# Temp_Probe_Section.net
KiCad netlist of a schematic drawn in Altium Designer
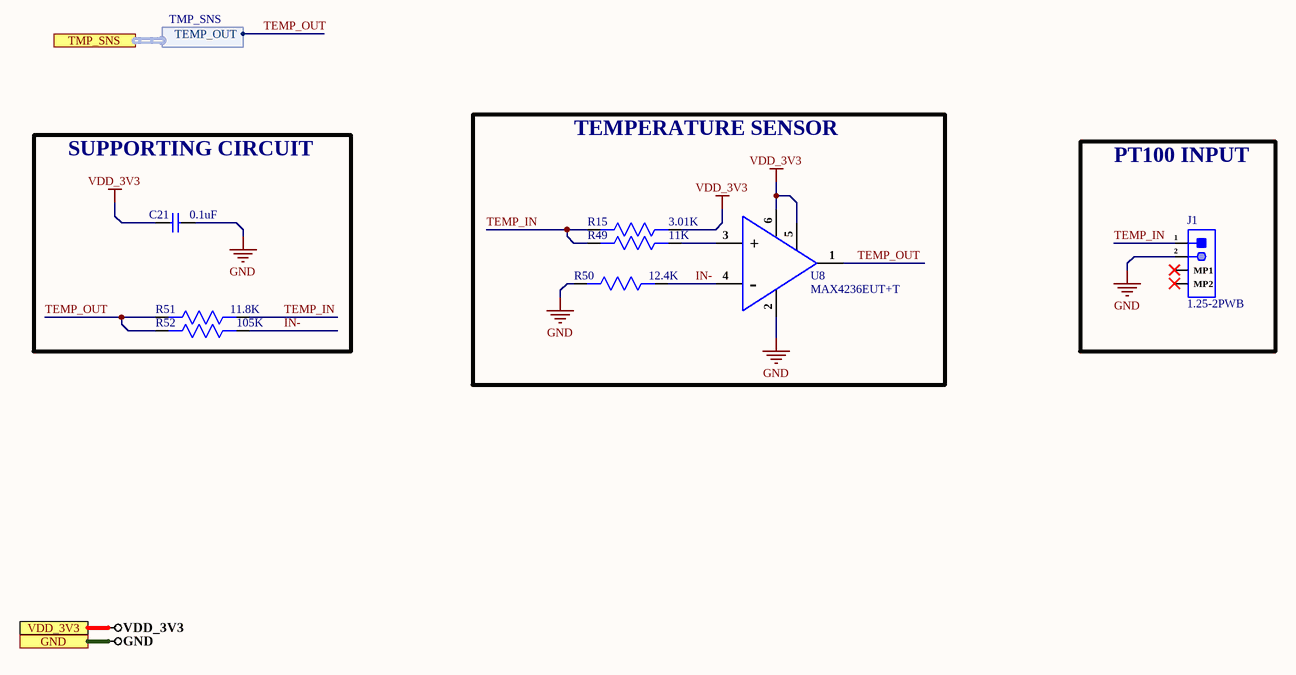
[diagram p0: Temp_Probe_Section.SchDoc]

(export (version "E")
  (design (tool "Eeschema 10.0.6"))
  (components
    (comp (ref "C21")
      (value "0.1uF")
      (footprint "Cap 0603")
      (description "Cap Ceramic 0.1uF 50VDC X7R 10% SMD 0603 Paper T/R")
      (fields
        (field (name "MANUFACTURER") "Samsung")
        (field (name "MANUFACTURER PART NUMBER") "CL10B104KB8NNNC")
      )
      (libsource (lib "Cole_Benson") (part "CL10B104KB8NNNC"))
    )
    (comp (ref "J1")
      (value "1.25-2PWB")
      (footprint "1.25-2PWB")
      (fields (field (name "MANUFACTURER") "DEALON") (field (name "LCSC PART NUMBER") "C2905009"))
      (libsource (lib "Cole_Benson") (part "1.25-2PWB"))
    )
    (comp (ref "R15")
      (value "3.01K")
      (footprint "Res0603")
      (description "RES SMD 3.01K OHM 1% 1/10W 0603")
      (fields
        (field (name "MANUFACTURER") "Panasonic")
        (field (name "MANUFACTURER PART NUMBER") "ERJ-3EKF3011V")
      )
      (libsource (lib "Cole_Benson") (part "ERJ3EKF3011V"))
    )
    (comp (ref "R49")
      (value "11K")
      (footprint "Res0603")
      (description "RES SMD 11K, 1%, 0.1W, 0603")
      (fields
        (field (name "MANUFACTURER") "Yageo")
        (field (name "MANUFACTURER PART NUMBER") "RC0603FR-0711KL")
      )
      (libsource (lib "Cole_Benson") (part "RC0603FR-0711KL"))
    )
    (comp (ref "R50")
      (value "12.4K")
      (footprint "Res0603")
      (description "RES SMD 12.4K OHM 1% 1/10W 0603")
      (fields
        (field (name "MANUFACTURER") "Yageo")
        (field (name "MANUFACTURER PART NUMBER") "RC0603FR-0712K4L")
      )
      (libsource (lib "Cole_Benson") (part "RC0603FR-0712K4L"))
    )
    (comp (ref "R51")
      (value "11.8K")
      (footprint "Res0603")
      (description "RES SMD 11.8K OHM 1% 1/10W 0603")
      (fields
        (field (name "MANUFACTURER") "Yageo")
        (field (name "MANUFACTURER PART NUMBER") "AC0603FR-0711K8L")
      )
      (libsource (lib "Cole_Benson") (part "AC0603FR-0711K8L"))
    )
    (comp (ref "R52")
      (value "105K")
      (footprint "Res0603")
      (description "RES SMD 105K OHM 1% 1/10W 0603")
      (fields
        (field (name "MANUFACTURER") "Yageo")
        (field (name "MANUFACTURER PART NUMBER") "RC0603FR-07105KL")
      )
      (libsource (lib "Cole_Benson") (part "RC0603FR-07105KL"))
    )
    (comp (ref "U8")
      (value "MAX4236EUT+T")
      (footprint "SOT-23-6")
      (description "IC OPAMP GP 1.7MHZ RRO SOT23-6")
      (fields (field (name "MANUFACTURER") "Maxim"))
      (libsource (lib "Cole_Benson") (part "MAX4236EUT+T"))
    )
  )
  (nets
    (net (code "2") (name "/IN-") (class "Default")
      (node (ref "R50") (pin "1") (pintype "passive"))
      (node (ref "R52") (pin "1") (pintype "passive"))
      (node (ref "U8") (pin "4") (pinfunction "-_4") (pintype "passive"))
    )
    (net (code "3") (name "/TEMP_IN") (class "Default")
      (node (ref "J1") (pin "1") (pinfunction "1_1") (pintype "passive"))
      (node (ref "R15") (pin "2") (pintype "passive"))
      (node (ref "R49") (pin "2") (pintype "passive"))
      (node (ref "R51") (pin "1") (pintype "passive"))
    )
    (net (code "4") (name "/TEMP_OUT") (class "Default")
      (node (ref "R51") (pin "2") (pintype "passive"))
      (node (ref "R52") (pin "2") (pintype "passive"))
      (node (ref "U8") (pin "1") (pinfunction "OUT_1") (pintype "passive"))
    )
    (net (code "6") (name "GND") (class "Default")
      (node (ref "C21") (pin "2") (pinfunction "2_2") (pintype "passive"))
      (node (ref "J1") (pin "2") (pinfunction "2_2") (pintype "passive"))
      (node (ref "R50") (pin "2") (pintype "passive"))
      (node (ref "U8") (pin "2") (pinfunction "VEE_2") (pintype "passive"))
    )
    (net (code "7") (name "Net-(U8-+)") (class "Default")
      (node (ref "R49") (pin "1") (pintype "passive"))
      (node (ref "U8") (pin "3") (pinfunction "+_3") (pintype "passive"))
    )
    (net (code "8") (name "VDD_3V3") (class "Default")
      (node (ref "C21") (pin "1") (pinfunction "1_1") (pintype "passive"))
      (node (ref "R15") (pin "1") (pintype "passive"))
      (node (ref "U8") (pin "5") (pinfunction "~{SHDN}_5") (pintype "passive"))
      (node (ref "U8") (pin "6") (pinfunction "VCC_6") (pintype "passive"))
    )
    (net (code "9") (name "unconnected-(J1-PadMP1)") (class "Default")
      (node (ref "J1") (pin "MP1") (pinfunction "MP1_MP1") (pintype "passive+no_connect"))
    )
    (net (code "10") (name "unconnected-(J1-PadMP2)") (class "Default")
      (node (ref "J1") (pin "MP2") (pinfunction "MP2_MP2") (pintype "passive+no_connect"))
    )
  )
)
